# RobotCtrl_Core.net
KiCad netlist of a schematic drawn in Altium Designer
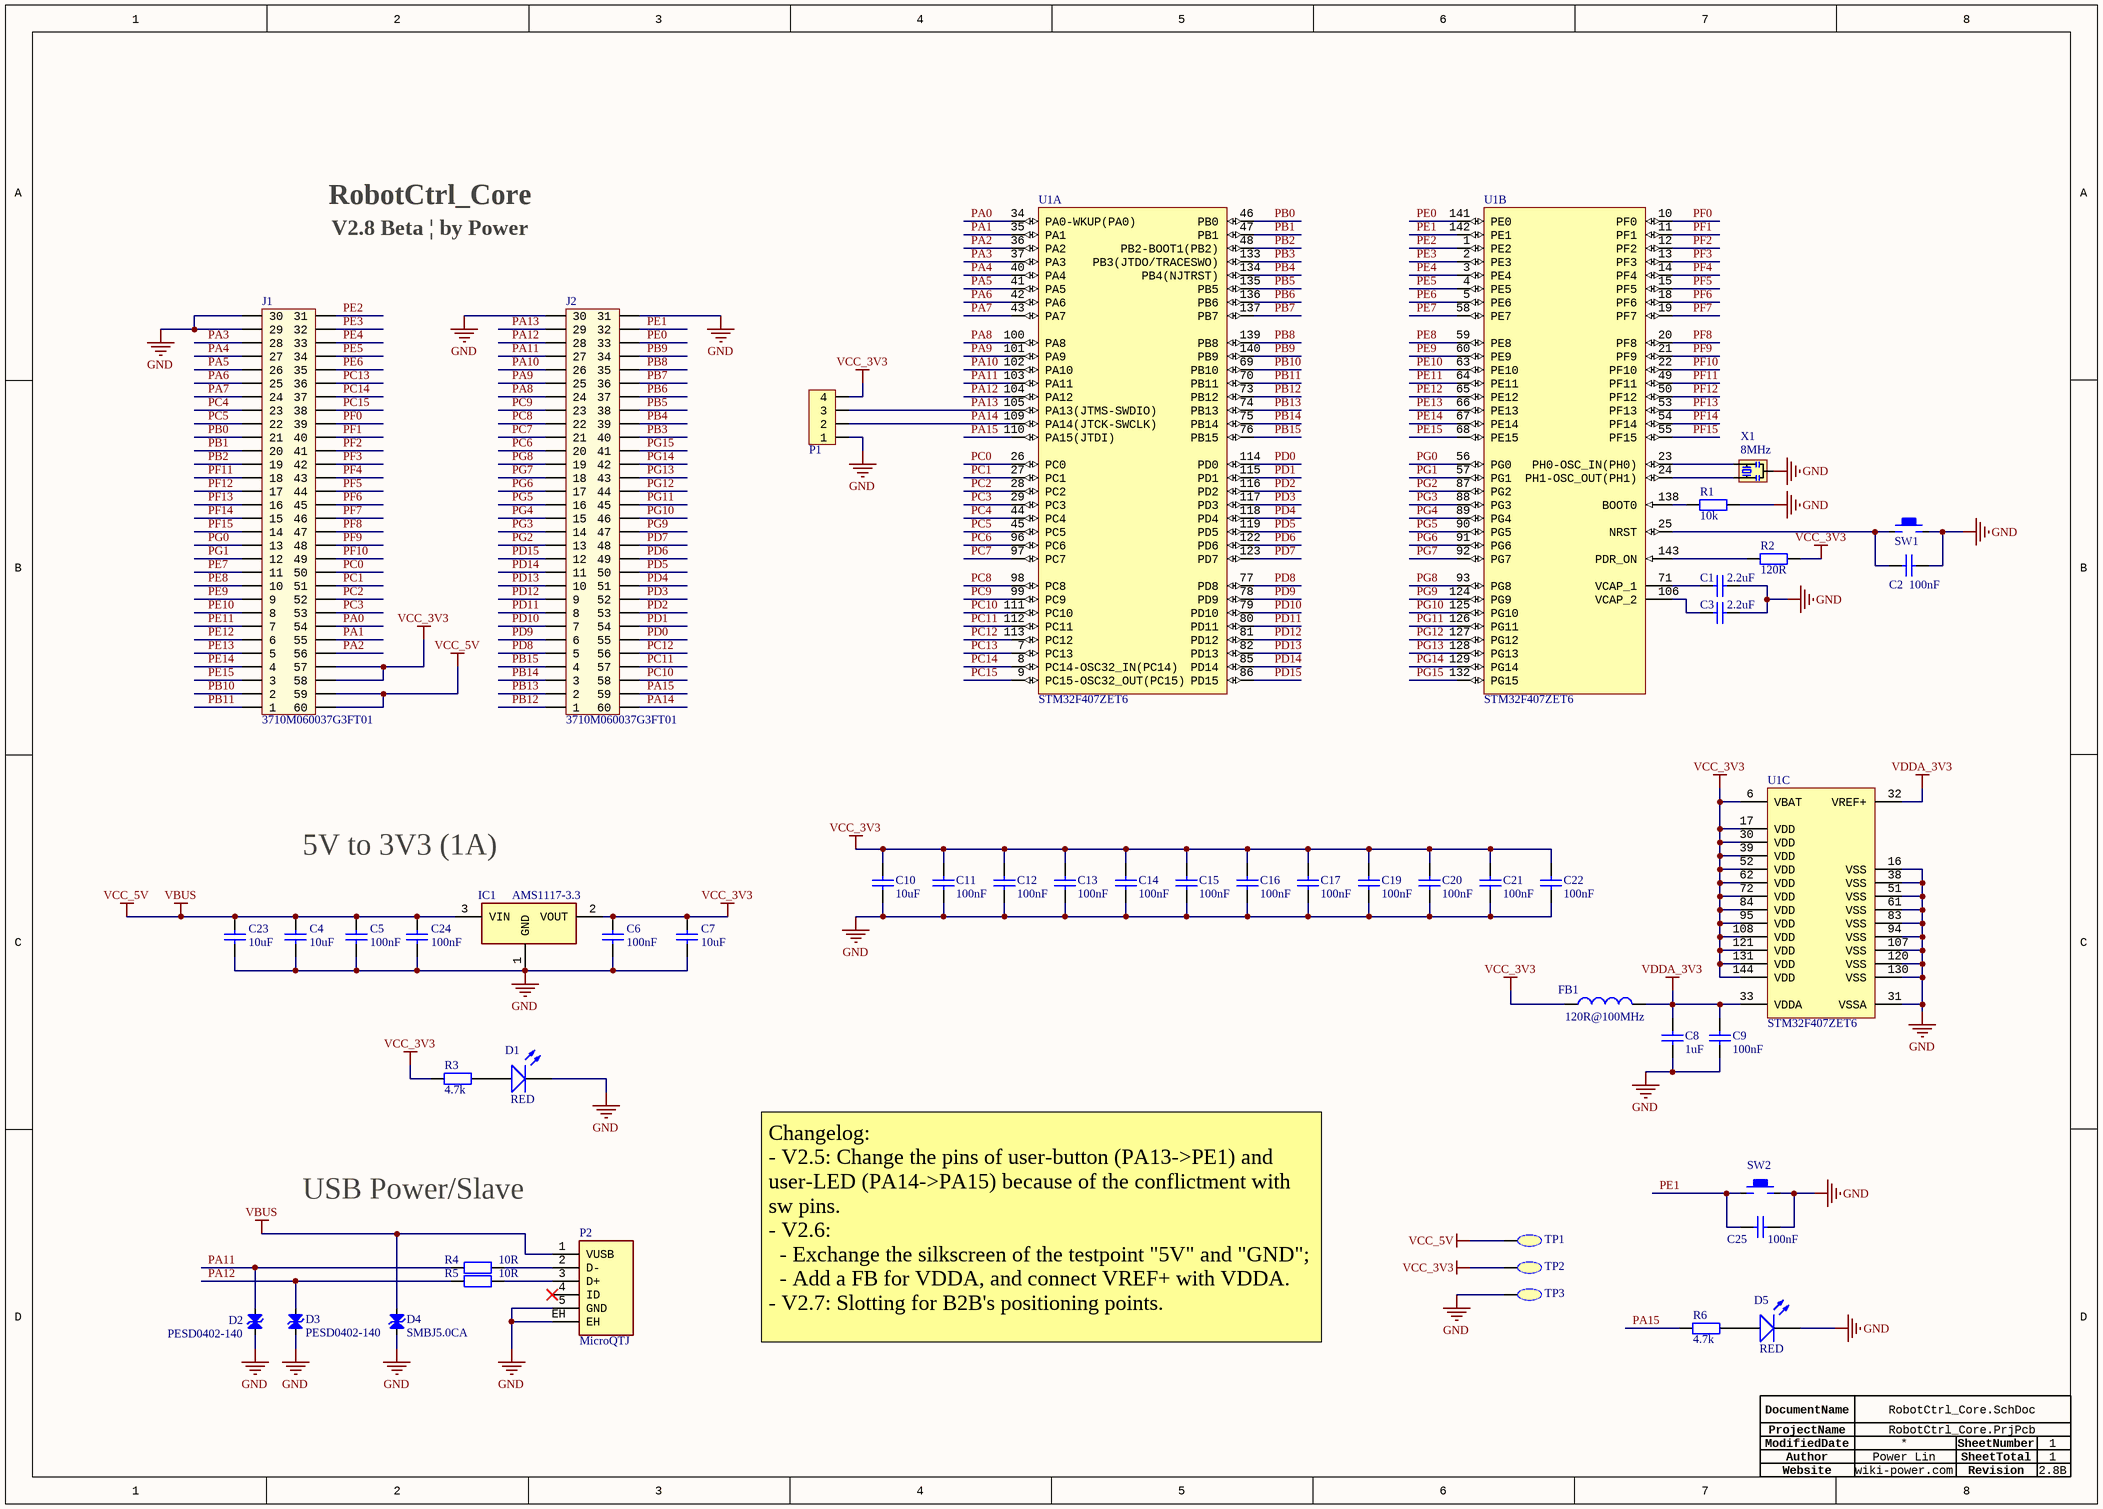
[diagram p0: RobotCtrl_Core.SchDoc]

(export (version "E")
  (design (tool "Eeschema 10.0.6"))
  (components
    (comp (ref "C1")
      (value "2.2uF")
      (footprint "CAP-0603")
      (description "贴片电容")
      (libsource (lib "Power_Lib_Altium") (part "CAP"))
    )
    (comp (ref "C2")
      (value "100nF")
      (footprint "CAP-0603")
      (description "贴片电容")
      (libsource (lib "Power_Lib_Altium") (part "CAP"))
    )
    (comp (ref "C3")
      (value "2.2uF")
      (footprint "CAP-0603")
      (description "贴片电容")
      (libsource (lib "Power_Lib_Altium") (part "CAP"))
    )
    (comp (ref "C4")
      (value "10uF")
      (footprint "CAP-0603")
      (description "贴片电容")
      (libsource (lib "Power_Lib_Altium") (part "CAP"))
    )
    (comp (ref "C5")
      (value "100nF")
      (footprint "CAP-0603")
      (description "贴片电容")
      (libsource (lib "Power_Lib_Altium") (part "CAP"))
    )
    (comp (ref "C6")
      (value "100nF")
      (footprint "CAP-0603")
      (description "贴片电容")
      (libsource (lib "Power_Lib_Altium") (part "CAP"))
    )
    (comp (ref "C7")
      (value "10uF")
      (footprint "CAP-0603")
      (description "贴片电容")
      (libsource (lib "Power_Lib_Altium") (part "CAP"))
    )
    (comp (ref "C8")
      (value "1uF")
      (footprint "CAP-0402")
      (description "贴片电容")
      (libsource (lib "Power_Lib_Altium") (part "CAP"))
    )
    (comp (ref "C9")
      (value "100nF")
      (footprint "CAP-0402")
      (description "贴片电容")
      (libsource (lib "Power_Lib_Altium") (part "CAP"))
    )
    (comp (ref "C10")
      (value "10uF")
      (footprint "CAP-0402")
      (description "贴片电容")
      (libsource (lib "Power_Lib_Altium") (part "CAP"))
    )
    (comp (ref "C11")
      (value "100nF")
      (footprint "CAP-0402")
      (description "贴片电容")
      (libsource (lib "Power_Lib_Altium") (part "CAP"))
    )
    (comp (ref "C12")
      (value "100nF")
      (footprint "CAP-0402")
      (description "贴片电容")
      (libsource (lib "Power_Lib_Altium") (part "CAP"))
    )
    (comp (ref "C13")
      (value "100nF")
      (footprint "CAP-0402")
      (description "贴片电容")
      (libsource (lib "Power_Lib_Altium") (part "CAP"))
    )
    (comp (ref "C14")
      (value "100nF")
      (footprint "CAP-0402")
      (description "贴片电容")
      (libsource (lib "Power_Lib_Altium") (part "CAP"))
    )
    (comp (ref "C15")
      (value "100nF")
      (footprint "CAP-0402")
      (description "贴片电容")
      (libsource (lib "Power_Lib_Altium") (part "CAP"))
    )
    (comp (ref "C16")
      (value "100nF")
      (footprint "CAP-0402")
      (description "贴片电容")
      (libsource (lib "Power_Lib_Altium") (part "CAP"))
    )
    (comp (ref "C17")
      (value "100nF")
      (footprint "CAP-0402")
      (description "贴片电容")
      (libsource (lib "Power_Lib_Altium") (part "CAP"))
    )
    (comp (ref "C19")
      (value "100nF")
      (footprint "CAP-0402")
      (description "贴片电容")
      (libsource (lib "Power_Lib_Altium") (part "CAP"))
    )
    (comp (ref "C20")
      (value "100nF")
      (footprint "CAP-0402")
      (description "贴片电容")
      (libsource (lib "Power_Lib_Altium") (part "CAP"))
    )
    (comp (ref "C21")
      (value "100nF")
      (footprint "CAP-0402")
      (description "贴片电容")
      (libsource (lib "Power_Lib_Altium") (part "CAP"))
    )
    (comp (ref "C22")
      (value "100nF")
      (footprint "CAP-0402")
      (description "贴片电容")
      (libsource (lib "Power_Lib_Altium") (part "CAP"))
    )
    (comp (ref "C23")
      (value "10uF")
      (footprint "CAP-0603")
      (description "贴片电容")
      (libsource (lib "Power_Lib_Altium") (part "CAP"))
    )
    (comp (ref "C24")
      (value "100nF")
      (footprint "CAP-0603")
      (description "贴片电容")
      (libsource (lib "Power_Lib_Altium") (part "CAP"))
    )
    (comp (ref "C25")
      (value "100nF")
      (footprint "CAP-0603")
      (description "贴片电容")
      (libsource (lib "Power_Lib_Altium") (part "CAP"))
    )
    (comp (ref "D1")
      (value "RED")
      (footprint "LED-0603")
      (description "发光二极管")
      (libsource (lib "Power_Lib_Altium") (part "LED"))
    )
    (comp (ref "D2")
      (value "PESD0402-140")
      (footprint "D-0402")
      (libsource (lib "Power_Lib_Altium") (part "TVS_C"))
    )
    (comp (ref "D3")
      (value "PESD0402-140")
      (footprint "D-0402")
      (libsource (lib "Power_Lib_Altium") (part "TVS_C"))
    )
    (comp (ref "D4")
      (value "SMBJ5.0CA")
      (footprint "DO-214AA/SMB")
      (description "Brightking / MDD")
      (libsource (lib "Power_Lib_Altium") (part "TVS_C"))
    )
    (comp (ref "D5")
      (value "RED")
      (footprint "LED-0603")
      (description "发光二极管")
      (libsource (lib "Power_Lib_Altium") (part "LED"))
    )
    (comp (ref "FB1")
      (value "120R@100MHz")
      (footprint "CAP-0402")
      (description "BLM15AG121SN1D")
      (libsource (lib "Power_Lib_Altium") (part "BEAD"))
    )
    (comp (ref "IC1")
      (value "AMS1117-3.3")
      (footprint "SOT-223")
      (description "AMS1117-3.3 1.0A")
      (fields (field (name "MANUFACTURER_PART_NUMBER") "SI2302DS") (field (name "RS PART NUMBER") "7983053P"))
      (libsource (lib "Power_Lib_Altium") (part "AMS1117"))
    )
    (comp (ref "J1")
      (value "3710M060037G3FT01")
      (footprint "3710M060037G3FT01")
      (description "B2B Connector")
      (libsource (lib "Power_Lib_Altium") (part "3710M/F"))
    )
    (comp (ref "J2")
      (value "3710M060037G3FT01")
      (footprint "3710M060037G3FT01")
      (description "B2B Connector")
      (libsource (lib "Power_Lib_Altium") (part "3710M/F"))
    )
    (comp (ref "P1")
      (value "HDR1x4_2.54")
      (footprint "HDR1X4_2.54")
      (description "Header")
      (libsource (lib "Power_Lib_Altium") (part "HDR1x4_2.54"))
    )
    (comp (ref "P2")
      (value "MicroQTJ")
      (footprint "USB-MICRO")
      (description "USB_MICRO")
      (libsource (lib "Power_Lib_Altium") (part "USB_MICRO"))
    )
    (comp (ref "R1")
      (value "10k")
      (footprint "R-0603")
      (description "贴片电阻")
      (libsource (lib "Power_Lib_Altium") (part "RES"))
    )
    (comp (ref "R2")
      (value "120R")
      (footprint "R-0603")
      (description "贴片电阻")
      (libsource (lib "Power_Lib_Altium") (part "RES"))
    )
    (comp (ref "R3")
      (value "4.7k")
      (footprint "R-0603")
      (description "贴片电阻")
      (libsource (lib "Power_Lib_Altium") (part "RES"))
    )
    (comp (ref "R4")
      (value "10R")
      (footprint "R-0603")
      (description "贴片电阻")
      (libsource (lib "") (part "RES_1"))
    )
    (comp (ref "R5")
      (value "10R")
      (footprint "R-0603")
      (description "贴片电阻")
      (libsource (lib "") (part "RES_1"))
    )
    (comp (ref "R6")
      (value "4.7k")
      (footprint "R-0603")
      (description "贴片电阻")
      (libsource (lib "Power_Lib_Altium") (part "RES"))
    )
    (comp (ref "SW1")
      (value "KEY")
      (footprint "KEY-4P-4.2*3.4*2.5")
      (description "按键开关")
      (libsource (lib "Power_Lib_Altium") (part "KEY"))
    )
    (comp (ref "SW2")
      (value "KEY")
      (footprint "KEY-4P-4.2*3.4*2.5")
      (description "按键开关")
      (libsource (lib "Power_Lib_Altium") (part "KEY"))
    )
    (comp (ref "TP1")
      (value "TestPoint")
      (footprint "TestPoint")
      (description "测试点")
      (libsource (lib "Power_Lib_Altium") (part "TestPoint"))
    )
    (comp (ref "TP2")
      (value "TestPoint")
      (footprint "TestPoint")
      (description "测试点")
      (libsource (lib "Power_Lib_Altium") (part "TestPoint"))
    )
    (comp (ref "TP3")
      (value "TestPoint")
      (footprint "TestPoint")
      (description "测试点")
      (libsource (lib "Power_Lib_Altium") (part "TestPoint"))
    )
    (comp (ref "U1")
      (value "STM32F407ZET6")
      (footprint "STM-LQFP144_N")
      (fields (field (name "MANUFACTURER") "STMicroelectronics"))
      (libsource (lib "Power_Lib_Altium") (part "STM32F407ZET6"))
    )
    (comp (ref "X1")
      (value "8MHz")
      (footprint "SMD3213-3P")
      (description "CSTCE8M00G15C99-R0")
      (libsource (lib "Power_Lib_Altium") (part "XTAL"))
    )
  )
  (nets
    (net (code "1") (name "/PA0") (class "Default")
      (node (ref "J1") (pin "54") (pinfunction "54_54") (pintype "passive"))
      (node (ref "U1") (pin "34") (pinfunction "PA0-WKUP(PA0)_34") (pintype "bidirectional"))
    )
    (net (code "2") (name "/PA1") (class "Default")
      (node (ref "J1") (pin "55") (pinfunction "55_55") (pintype "passive"))
      (node (ref "U1") (pin "35") (pinfunction "PA1_35") (pintype "bidirectional"))
    )
    (net (code "3") (name "/PA2") (class "Default")
      (node (ref "J1") (pin "56") (pinfunction "56_56") (pintype "passive"))
      (node (ref "U1") (pin "36") (pinfunction "PA2_36") (pintype "bidirectional"))
    )
    (net (code "4") (name "/PA3") (class "Default")
      (node (ref "J1") (pin "28") (pinfunction "28_28") (pintype "passive"))
      (node (ref "U1") (pin "37") (pinfunction "PA3_37") (pintype "bidirectional"))
    )
    (net (code "5") (name "/PA4") (class "Default")
      (node (ref "J1") (pin "27") (pinfunction "27_27") (pintype "passive"))
      (node (ref "U1") (pin "40") (pinfunction "PA4_40") (pintype "bidirectional"))
    )
    (net (code "6") (name "/PA5") (class "Default")
      (node (ref "J1") (pin "26") (pinfunction "26_26") (pintype "passive"))
      (node (ref "U1") (pin "41") (pinfunction "PA5_41") (pintype "bidirectional"))
    )
    (net (code "7") (name "/PA6") (class "Default")
      (node (ref "J1") (pin "25") (pinfunction "25_25") (pintype "passive"))
      (node (ref "U1") (pin "42") (pinfunction "PA6_42") (pintype "bidirectional"))
    )
    (net (code "8") (name "/PA7") (class "Default")
      (node (ref "J1") (pin "24") (pinfunction "24_24") (pintype "passive"))
      (node (ref "U1") (pin "43") (pinfunction "PA7_43") (pintype "bidirectional"))
    )
    (net (code "9") (name "/PA8") (class "Default")
      (node (ref "J2") (pin "24") (pinfunction "24_24") (pintype "passive"))
      (node (ref "U1") (pin "100") (pinfunction "PA8_100") (pintype "bidirectional"))
    )
    (net (code "10") (name "/PA9") (class "Default")
      (node (ref "J2") (pin "25") (pinfunction "25_25") (pintype "passive"))
      (node (ref "U1") (pin "101") (pinfunction "PA9_101") (pintype "bidirectional"))
    )
    (net (code "11") (name "/PA10") (class "Default")
      (node (ref "J2") (pin "26") (pinfunction "26_26") (pintype "passive"))
      (node (ref "U1") (pin "102") (pinfunction "PA10_102") (pintype "bidirectional"))
    )
    (net (code "12") (name "/PA11") (class "Default")
      (node (ref "D2") (pin "2") (pinfunction "2_2") (pintype "passive"))
      (node (ref "J2") (pin "27") (pinfunction "27_27") (pintype "passive"))
      (node (ref "R4") (pin "1") (pinfunction "1_1") (pintype "passive"))
      (node (ref "U1") (pin "103") (pinfunction "PA11_103") (pintype "bidirectional"))
    )
    (net (code "13") (name "/PA12") (class "Default")
      (node (ref "D3") (pin "2") (pinfunction "2_2") (pintype "passive"))
      (node (ref "J2") (pin "28") (pinfunction "28_28") (pintype "passive"))
      (node (ref "R5") (pin "1") (pinfunction "1_1") (pintype "passive"))
      (node (ref "U1") (pin "104") (pinfunction "PA12_104") (pintype "bidirectional"))
    )
    (net (code "14") (name "/PA13") (class "Default")
      (node (ref "J2") (pin "29") (pinfunction "29_29") (pintype "passive"))
      (node (ref "P1") (pin "3") (pinfunction "3_3") (pintype "passive"))
      (node (ref "U1") (pin "105") (pinfunction "PA13(JTMS-SWDIO)_105") (pintype "bidirectional"))
    )
    (net (code "15") (name "/PA14") (class "Default")
      (node (ref "J2") (pin "60") (pinfunction "60_60") (pintype "passive"))
      (node (ref "P1") (pin "2") (pinfunction "2_2") (pintype "passive"))
      (node (ref "U1") (pin "109") (pinfunction "PA14(JTCK-SWCLK)_109") (pintype "bidirectional"))
    )
    (net (code "16") (name "/PA15") (class "Default")
      (node (ref "J2") (pin "59") (pinfunction "59_59") (pintype "passive"))
      (node (ref "R6") (pin "2") (pinfunction "2_2") (pintype "passive"))
      (node (ref "U1") (pin "110") (pinfunction "PA15(JTDI)_110") (pintype "bidirectional"))
    )
    (net (code "17") (name "/PB0") (class "Default")
      (node (ref "J1") (pin "21") (pinfunction "21_21") (pintype "passive"))
      (node (ref "U1") (pin "46") (pinfunction "PB0_46") (pintype "bidirectional"))
    )
    (net (code "18") (name "/PB1") (class "Default")
      (node (ref "J1") (pin "20") (pinfunction "20_20") (pintype "passive"))
      (node (ref "U1") (pin "47") (pinfunction "PB1_47") (pintype "bidirectional"))
    )
    (net (code "19") (name "/PB2") (class "Default")
      (node (ref "J1") (pin "19") (pinfunction "19_19") (pintype "passive"))
      (node (ref "U1") (pin "48") (pinfunction "PB2-BOOT1(PB2)_48") (pintype "bidirectional"))
    )
    (net (code "20") (name "/PB3") (class "Default")
      (node (ref "J2") (pin "40") (pinfunction "40_40") (pintype "passive"))
      (node (ref "U1") (pin "133") (pinfunction "PB3(JTDO/TRACESWO)_133") (pintype "bidirectional"))
    )
    (net (code "21") (name "/PB4") (class "Default")
      (node (ref "J2") (pin "39") (pinfunction "39_39") (pintype "passive"))
      (node (ref "U1") (pin "134") (pinfunction "PB4(NJTRST)_134") (pintype "bidirectional"))
    )
    (net (code "22") (name "/PB5") (class "Default")
      (node (ref "J2") (pin "38") (pinfunction "38_38") (pintype "passive"))
      (node (ref "U1") (pin "135") (pinfunction "PB5_135") (pintype "bidirectional"))
    )
    (net (code "23") (name "/PB6") (class "Default")
      (node (ref "J2") (pin "37") (pinfunction "37_37") (pintype "passive"))
      (node (ref "U1") (pin "136") (pinfunction "PB6_136") (pintype "bidirectional"))
    )
    (net (code "24") (name "/PB7") (class "Default")
      (node (ref "J2") (pin "36") (pinfunction "36_36") (pintype "passive"))
      (node (ref "U1") (pin "137") (pinfunction "PB7_137") (pintype "bidirectional"))
    )
    (net (code "25") (name "/PB8") (class "Default")
      (node (ref "J2") (pin "35") (pinfunction "35_35") (pintype "passive"))
      (node (ref "U1") (pin "139") (pinfunction "PB8_139") (pintype "bidirectional"))
    )
    (net (code "26") (name "/PB9") (class "Default")
      (node (ref "J2") (pin "34") (pinfunction "34_34") (pintype "passive"))
      (node (ref "U1") (pin "140") (pinfunction "PB9_140") (pintype "bidirectional"))
    )
    (net (code "27") (name "/PB10") (class "Default")
      (node (ref "J1") (pin "2") (pinfunction "2_2") (pintype "passive"))
      (node (ref "U1") (pin "69") (pinfunction "PB10_69") (pintype "bidirectional"))
    )
    (net (code "28") (name "/PB11") (class "Default")
      (node (ref "J1") (pin "1") (pinfunction "1_1") (pintype "passive"))
      (node (ref "U1") (pin "70") (pinfunction "PB11_70") (pintype "bidirectional"))
    )
    (net (code "29") (name "/PB12") (class "Default")
      (node (ref "J2") (pin "1") (pinfunction "1_1") (pintype "passive"))
      (node (ref "U1") (pin "73") (pinfunction "PB12_73") (pintype "bidirectional"))
    )
    (net (code "30") (name "/PB13") (class "Default")
      (node (ref "J2") (pin "2") (pinfunction "2_2") (pintype "passive"))
      (node (ref "U1") (pin "74") (pinfunction "PB13_74") (pintype "bidirectional"))
    )
    (net (code "31") (name "/PB14") (class "Default")
      (node (ref "J2") (pin "3") (pinfunction "3_3") (pintype "passive"))
      (node (ref "U1") (pin "75") (pinfunction "PB14_75") (pintype "bidirectional"))
    )
    (net (code "32") (name "/PB15") (class "Default")
      (node (ref "J2") (pin "4") (pinfunction "4_4") (pintype "passive"))
      (node (ref "U1") (pin "76") (pinfunction "PB15_76") (pintype "bidirectional"))
    )
    (net (code "33") (name "/PC0") (class "Default")
      (node (ref "J1") (pin "50") (pinfunction "50_50") (pintype "passive"))
      (node (ref "U1") (pin "26") (pinfunction "PC0_26") (pintype "bidirectional"))
    )
    (net (code "34") (name "/PC1") (class "Default")
      (node (ref "J1") (pin "51") (pinfunction "51_51") (pintype "passive"))
      (node (ref "U1") (pin "27") (pinfunction "PC1_27") (pintype "bidirectional"))
    )
    (net (code "35") (name "/PC2") (class "Default")
      (node (ref "J1") (pin "52") (pinfunction "52_52") (pintype "passive"))
      (node (ref "U1") (pin "28") (pinfunction "PC2_28") (pintype "bidirectional"))
    )
    (net (code "36") (name "/PC3") (class "Default")
      (node (ref "J1") (pin "53") (pinfunction "53_53") (pintype "passive"))
      (node (ref "U1") (pin "29") (pinfunction "PC3_29") (pintype "bidirectional"))
    )
    (net (code "37") (name "/PC4") (class "Default")
      (node (ref "J1") (pin "23") (pinfunction "23_23") (pintype "passive"))
      (node (ref "U1") (pin "44") (pinfunction "PC4_44") (pintype "bidirectional"))
    )
    (net (code "38") (name "/PC5") (class "Default")
      (node (ref "J1") (pin "22") (pinfunction "22_22") (pintype "passive"))
      (node (ref "U1") (pin "45") (pinfunction "PC5_45") (pintype "bidirectional"))
    )
    (net (code "39") (name "/PC6") (class "Default")
      (node (ref "J2") (pin "20") (pinfunction "20_20") (pintype "passive"))
      (node (ref "U1") (pin "96") (pinfunction "PC6_96") (pintype "bidirectional"))
    )
    (net (code "40") (name "/PC7") (class "Default")
      (node (ref "J2") (pin "21") (pinfunction "21_21") (pintype "passive"))
      (node (ref "U1") (pin "97") (pinfunction "PC7_97") (pintype "bidirectional"))
    )
    (net (code "41") (name "/PC8") (class "Default")
      (node (ref "J2") (pin "22") (pinfunction "22_22") (pintype "passive"))
      (node (ref "U1") (pin "98") (pinfunction "PC8_98") (pintype "bidirectional"))
    )
    (net (code "42") (name "/PC9") (class "Default")
      (node (ref "J2") (pin "23") (pinfunction "23_23") (pintype "passive"))
      (node (ref "U1") (pin "99") (pinfunction "PC9_99") (pintype "bidirectional"))
    )
    (net (code "43") (name "/PC10") (class "Default")
      (node (ref "J2") (pin "58") (pinfunction "58_58") (pintype "passive"))
      (node (ref "U1") (pin "111") (pinfunction "PC10_111") (pintype "bidirectional"))
    )
    (net (code "44") (name "/PC11") (class "Default")
      (node (ref "J2") (pin "57") (pinfunction "57_57") (pintype "passive"))
      (node (ref "U1") (pin "112") (pinfunction "PC11_112") (pintype "bidirectional"))
    )
    (net (code "45") (name "/PC12") (class "Default")
      (node (ref "J2") (pin "56") (pinfunction "56_56") (pintype "passive"))
      (node (ref "U1") (pin "113") (pinfunction "PC12_113") (pintype "bidirectional"))
    )
    (net (code "46") (name "/PC13") (class "Default")
      (node (ref "J1") (pin "36") (pinfunction "36_36") (pintype "passive"))
      (node (ref "U1") (pin "7") (pinfunction "PC13_7") (pintype "bidirectional"))
    )
    (net (code "47") (name "/PC14") (class "Default")
      (node (ref "J1") (pin "37") (pinfunction "37_37") (pintype "passive"))
      (node (ref "U1") (pin "8") (pinfunction "PC14-OSC32_IN(PC14)_8") (pintype "bidirectional"))
    )
    (net (code "48") (name "/PC15") (class "Default")
      (node (ref "J1") (pin "38") (pinfunction "38_38") (pintype "passive"))
      (node (ref "U1") (pin "9") (pinfunction "PC15-OSC32_OUT(PC15)_9") (pintype "bidirectional"))
    )
    (net (code "49") (name "/PD0") (class "Default")
      (node (ref "J2") (pin "55") (pinfunction "55_55") (pintype "passive"))
      (node (ref "U1") (pin "114") (pinfunction "PD0_114") (pintype "bidirectional"))
    )
    (net (code "50") (name "/PD1") (class "Default")
      (node (ref "J2") (pin "54") (pinfunction "54_54") (pintype "passive"))
      (node (ref "U1") (pin "115") (pinfunction "PD1_115") (pintype "bidirectional"))
    )
    (net (code "51") (name "/PD2") (class "Default")
      (node (ref "J2") (pin "53") (pinfunction "53_53") (pintype "passive"))
      (node (ref "U1") (pin "116") (pinfunction "PD2_116") (pintype "bidirectional"))
    )
    (net (code "52") (name "/PD3") (class "Default")
      (node (ref "J2") (pin "52") (pinfunction "52_52") (pintype "passive"))
      (node (ref "U1") (pin "117") (pinfunction "PD3_117") (pintype "bidirectional"))
    )
    (net (code "53") (name "/PD4") (class "Default")
      (node (ref "J2") (pin "51") (pinfunction "51_51") (pintype "passive"))
      (node (ref "U1") (pin "118") (pinfunction "PD4_118") (pintype "bidirectional"))
    )
    (net (code "54") (name "/PD5") (class "Default")
      (node (ref "J2") (pin "50") (pinfunction "50_50") (pintype "passive"))
      (node (ref "U1") (pin "119") (pinfunction "PD5_119") (pintype "bidirectional"))
    )
    (net (code "55") (name "/PD6") (class "Default")
      (node (ref "J2") (pin "49") (pinfunction "49_49") (pintype "passive"))
      (node (ref "U1") (pin "122") (pinfunction "PD6_122") (pintype "bidirectional"))
    )
    (net (code "56") (name "/PD7") (class "Default")
      (node (ref "J2") (pin "48") (pinfunction "48_48") (pintype "passive"))
      (node (ref "U1") (pin "123") (pinfunction "PD7_123") (pintype "bidirectional"))
    )
    (net (code "57") (name "/PD8") (class "Default")
      (node (ref "J2") (pin "5") (pinfunction "5_5") (pintype "passive"))
      (node (ref "U1") (pin "77") (pinfunction "PD8_77") (pintype "bidirectional"))
    )
    (net (code "58") (name "/PD9") (class "Default")
      (node (ref "J2") (pin "6") (pinfunction "6_6") (pintype "passive"))
      (node (ref "U1") (pin "78") (pinfunction "PD9_78") (pintype "bidirectional"))
    )
    (net (code "59") (name "/PD10") (class "Default")
      (node (ref "J2") (pin "7") (pinfunction "7_7") (pintype "passive"))
      (node (ref "U1") (pin "79") (pinfunction "PD10_79") (pintype "bidirectional"))
    )
    (net (code "60") (name "/PD11") (class "Default")
      (node (ref "J2") (pin "8") (pinfunction "8_8") (pintype "passive"))
      (node (ref "U1") (pin "80") (pinfunction "PD11_80") (pintype "bidirectional"))
    )
    (net (code "61") (name "/PD12") (class "Default")
      (node (ref "J2") (pin "9") (pinfunction "9_9") (pintype "passive"))
      (node (ref "U1") (pin "81") (pinfunction "PD12_81") (pintype "bidirectional"))
    )
    (net (code "62") (name "/PD13") (class "Default")
      (node (ref "J2") (pin "10") (pinfunction "10_10") (pintype "passive"))
      (node (ref "U1") (pin "82") (pinfunction "PD13_82") (pintype "bidirectional"))
    )
    (net (code "63") (name "/PD14") (class "Default")
      (node (ref "J2") (pin "11") (pinfunction "11_11") (pintype "passive"))
      (node (ref "U1") (pin "85") (pinfunction "PD14_85") (pintype "bidirectional"))
    )
    (net (code "64") (name "/PD15") (class "Default")
      (node (ref "J2") (pin "12") (pinfunction "12_12") (pintype "passive"))
      (node (ref "U1") (pin "86") (pinfunction "PD15_86") (pintype "bidirectional"))
    )
    (net (code "65") (name "/PE0") (class "Default")
      (node (ref "J2") (pin "33") (pinfunction "33_33") (pintype "passive"))
      (node (ref "U1") (pin "141") (pinfunction "PE0_141") (pintype "bidirectional"))
    )
    (net (code "66") (name "/PE1") (class "Default")
      (node (ref "C25") (pin "2") (pinfunction "2_2") (pintype "passive"))
      (node (ref "J2") (pin "32") (pinfunction "32_32") (pintype "passive"))
      (node (ref "SW2") (pin "1") (pinfunction "1_1") (pintype "passive"))
      (node (ref "U1") (pin "142") (pinfunction "PE1_142") (pintype "bidirectional"))
    )
    (net (code "67") (name "/PE2") (class "Default")
      (node (ref "J1") (pin "31") (pinfunction "31_31") (pintype "passive"))
      (node (ref "U1") (pin "1") (pinfunction "PE2_1") (pintype "bidirectional"))
    )
    (net (code "68") (name "/PE3") (class "Default")
      (node (ref "J1") (pin "32") (pinfunction "32_32") (pintype "passive"))
      (node (ref "U1") (pin "2") (pinfunction "PE3_2") (pintype "bidirectional"))
    )
    (net (code "69") (name "/PE4") (class "Default")
      (node (ref "J1") (pin "33") (pinfunction "33_33") (pintype "passive"))
      (node (ref "U1") (pin "3") (pinfunction "PE4_3") (pintype "bidirectional"))
    )
    (net (code "70") (name "/PE5") (class "Default")
      (node (ref "J1") (pin "34") (pinfunction "34_34") (pintype "passive"))
      (node (ref "U1") (pin "4") (pinfunction "PE5_4") (pintype "bidirectional"))
    )
    (net (code "71") (name "/PE6") (class "Default")
      (node (ref "J1") (pin "35") (pinfunction "35_35") (pintype "passive"))
      (node (ref "U1") (pin "5") (pinfunction "PE6_5") (pintype "bidirectional"))
    )
    (net (code "72") (name "/PE7") (class "Default")
      (node (ref "J1") (pin "11") (pinfunction "11_11") (pintype "passive"))
      (node (ref "U1") (pin "58") (pinfunction "PE7_58") (pintype "bidirectional"))
    )
    (net (code "73") (name "/PE8") (class "Default")
      (node (ref "J1") (pin "10") (pinfunction "10_10") (pintype "passive"))
      (node (ref "U1") (pin "59") (pinfunction "PE8_59") (pintype "bidirectional"))
    )
    (net (code "74") (name "/PE9") (class "Default")
      (node (ref "J1") (pin "9") (pinfunction "9_9") (pintype "passive"))
      (node (ref "U1") (pin "60") (pinfunction "PE9_60") (pintype "bidirectional"))
    )
    (net (code "75") (name "/PE10") (class "Default")
      (node (ref "J1") (pin "8") (pinfunction "8_8") (pintype "passive"))
      (node (ref "U1") (pin "63") (pinfunction "PE10_63") (pintype "bidirectional"))
    )
    (net (code "76") (name "/PE11") (class "Default")
      (node (ref "J1") (pin "7") (pinfunction "7_7") (pintype "passive"))
      (node (ref "U1") (pin "64") (pinfunction "PE11_64") (pintype "bidirectional"))
    )
    (net (code "77") (name "/PE12") (class "Default")
      (node (ref "J1") (pin "6") (pinfunction "6_6") (pintype "passive"))
      (node (ref "U1") (pin "65") (pinfunction "PE12_65") (pintype "bidirectional"))
    )
    (net (code "78") (name "/PE13") (class "Default")
      (node (ref "J1") (pin "5") (pinfunction "5_5") (pintype "passive"))
      (node (ref "U1") (pin "66") (pinfunction "PE13_66") (pintype "bidirectional"))
    )
    (net (code "79") (name "/PE14") (class "Default")
      (node (ref "J1") (pin "4") (pinfunction "4_4") (pintype "passive"))
      (node (ref "U1") (pin "67") (pinfunction "PE14_67") (pintype "bidirectional"))
    )
    (net (code "80") (name "/PE15") (class "Default")
      (node (ref "J1") (pin "3") (pinfunction "3_3") (pintype "passive"))
      (node (ref "U1") (pin "68") (pinfunction "PE15_68") (pintype "bidirectional"))
    )
    (net (code "81") (name "/PF0") (class "Default")
      (node (ref "J1") (pin "39") (pinfunction "39_39") (pintype "passive"))
      (node (ref "U1") (pin "10") (pinfunction "PF0_10") (pintype "bidirectional"))
    )
    (net (code "82") (name "/PF1") (class "Default")
      (node (ref "J1") (pin "40") (pinfunction "40_40") (pintype "passive"))
      (node (ref "U1") (pin "11") (pinfunction "PF1_11") (pintype "bidirectional"))
    )
    (net (code "83") (name "/PF2") (class "Default")
      (node (ref "J1") (pin "41") (pinfunction "41_41") (pintype "passive"))
      (node (ref "U1") (pin "12") (pinfunction "PF2_12") (pintype "bidirectional"))
    )
    (net (code "84") (name "/PF3") (class "Default")
      (node (ref "J1") (pin "42") (pinfunction "42_42") (pintype "passive"))
      (node (ref "U1") (pin "13") (pinfunction "PF3_13") (pintype "bidirectional"))
    )
    (net (code "85") (name "/PF4") (class "Default")
      (node (ref "J1") (pin "43") (pinfunction "43_43") (pintype "passive"))
      (node (ref "U1") (pin "14") (pinfunction "PF4_14") (pintype "bidirectional"))
    )
    (net (code "86") (name "/PF5") (class "Default")
      (node (ref "J1") (pin "44") (pinfunction "44_44") (pintype "passive"))
      (node (ref "U1") (pin "15") (pinfunction "PF5_15") (pintype "bidirectional"))
    )
    (net (code "87") (name "/PF6") (class "Default")
      (node (ref "J1") (pin "45") (pinfunction "45_45") (pintype "passive"))
      (node (ref "U1") (pin "18") (pinfunction "PF6_18") (pintype "bidirectional"))
    )
    (net (code "88") (name "/PF7") (class "Default")
      (node (ref "J1") (pin "46") (pinfunction "46_46") (pintype "passive"))
      (node (ref "U1") (pin "19") (pinfunction "PF7_19") (pintype "bidirectional"))
    )
    (net (code "89") (name "/PF8") (class "Default")
      (node (ref "J1") (pin "47") (pinfunction "47_47") (pintype "passive"))
      (node (ref "U1") (pin "20") (pinfunction "PF8_20") (pintype "bidirectional"))
    )
    (net (code "90") (name "/PF9") (class "Default")
      (node (ref "J1") (pin "48") (pinfunction "48_48") (pintype "passive"))
      (node (ref "U1") (pin "21") (pinfunction "PF9_21") (pintype "bidirectional"))
    )
    (net (code "91") (name "/PF10") (class "Default")
      (node (ref "J1") (pin "49") (pinfunction "49_49") (pintype "passive"))
      (node (ref "U1") (pin "22") (pinfunction "PF10_22") (pintype "bidirectional"))
    )
    (net (code "92") (name "/PF11") (class "Default")
      (node (ref "J1") (pin "18") (pinfunction "18_18") (pintype "passive"))
      (node (ref "U1") (pin "49") (pinfunction "PF11_49") (pintype "bidirectional"))
    )
    (net (code "93") (name "/PF12") (class "Default")
      (node (ref "J1") (pin "17") (pinfunction "17_17") (pintype "passive"))
      (node (ref "U1") (pin "50") (pinfunction "PF12_50") (pintype "bidirectional"))
    )
    (net (code "94") (name "/PF13") (class "Default")
      (node (ref "J1") (pin "16") (pinfunction "16_16") (pintype "passive"))
      (node (ref "U1") (pin "53") (pinfunction "PF13_53") (pintype "bidirectional"))
    )
    (net (code "95") (name "/PF14") (class "Default")
      (node (ref "J1") (pin "15") (pinfunction "15_15") (pintype "passive"))
      (node (ref "U1") (pin "54") (pinfunction "PF14_54") (pintype "bidirectional"))
    )
    (net (code "96") (name "/PF15") (class "Default")
      (node (ref "J1") (pin "14") (pinfunction "14_14") (pintype "passive"))
      (node (ref "U1") (pin "55") (pinfunction "PF15_55") (pintype "bidirectional"))
    )
    (net (code "97") (name "/PG0") (class "Default")
      (node (ref "J1") (pin "13") (pinfunction "13_13") (pintype "passive"))
      (node (ref "U1") (pin "56") (pinfunction "PG0_56") (pintype "bidirectional"))
    )
    (net (code "98") (name "/PG1") (class "Default")
      (node (ref "J1") (pin "12") (pinfunction "12_12") (pintype "passive"))
      (node (ref "U1") (pin "57") (pinfunction "PG1_57") (pintype "bidirectional"))
    )
    (net (code "99") (name "/PG2") (class "Default")
      (node (ref "J2") (pin "13") (pinfunction "13_13") (pintype "passive"))
      (node (ref "U1") (pin "87") (pinfunction "PG2_87") (pintype "bidirectional"))
    )
    (net (code "100") (name "/PG3") (class "Default")
      (node (ref "J2") (pin "14") (pinfunction "14_14") (pintype "passive"))
      (node (ref "U1") (pin "88") (pinfunction "PG3_88") (pintype "bidirectional"))
    )
    (net (code "101") (name "/PG4") (class "Default")
      (node (ref "J2") (pin "15") (pinfunction "15_15") (pintype "passive"))
      (node (ref "U1") (pin "89") (pinfunction "PG4_89") (pintype "bidirectional"))
    )
    (net (code "102") (name "/PG5") (class "Default")
      (node (ref "J2") (pin "16") (pinfunction "16_16") (pintype "passive"))
      (node (ref "U1") (pin "90") (pinfunction "PG5_90") (pintype "bidirectional"))
    )
    (net (code "103") (name "/PG6") (class "Default")
      (node (ref "J2") (pin "17") (pinfunction "17_17") (pintype "passive"))
      (node (ref "U1") (pin "91") (pinfunction "PG6_91") (pintype "bidirectional"))
    )
    (net (code "104") (name "/PG7") (class "Default")
      (node (ref "J2") (pin "18") (pinfunction "18_18") (pintype "passive"))
      (node (ref "U1") (pin "92") (pinfunction "PG7_92") (pintype "bidirectional"))
    )
    (net (code "105") (name "/PG8") (class "Default")
      (node (ref "J2") (pin "19") (pinfunction "19_19") (pintype "passive"))
      (node (ref "U1") (pin "93") (pinfunction "PG8_93") (pintype "bidirectional"))
    )
    (net (code "106") (name "/PG9") (class "Default")
      (node (ref "J2") (pin "47") (pinfunction "47_47") (pintype "passive"))
      (node (ref "U1") (pin "124") (pinfunction "PG9_124") (pintype "bidirectional"))
    )
    (net (code "107") (name "/PG10") (class "Default")
      (node (ref "J2") (pin "46") (pinfunction "46_46") (pintype "passive"))
      (node (ref "U1") (pin "125") (pinfunction "PG10_125") (pintype "bidirectional"))
    )
    (net (code "108") (name "/PG11") (class "Default")
      (node (ref "J2") (pin "45") (pinfunction "45_45") (pintype "passive"))
      (node (ref "U1") (pin "126") (pinfunction "PG11_126") (pintype "bidirectional"))
    )
    (net (code "109") (name "/PG12") (class "Default")
      (node (ref "J2") (pin "44") (pinfunction "44_44") (pintype "passive"))
      (node (ref "U1") (pin "127") (pinfunction "PG12_127") (pintype "bidirectional"))
    )
    (net (code "110") (name "/PG13") (class "Default")
      (node (ref "J2") (pin "43") (pinfunction "43_43") (pintype "passive"))
      (node (ref "U1") (pin "128") (pinfunction "PG13_128") (pintype "bidirectional"))
    )
    (net (code "111") (name "/PG14") (class "Default")
      (node (ref "J2") (pin "42") (pinfunction "42_42") (pintype "passive"))
      (node (ref "U1") (pin "129") (pinfunction "PG14_129") (pintype "bidirectional"))
    )
    (net (code "112") (name "/PG15") (class "Default")
      (node (ref "J2") (pin "41") (pinfunction "41_41") (pintype "passive"))
      (node (ref "U1") (pin "132") (pinfunction "PG15_132") (pintype "bidirectional"))
    )
    (net (code "113") (name "GND") (class "Default")
      (node (ref "C1") (pin "2") (pinfunction "2_2") (pintype "passive"))
      (node (ref "C10") (pin "1") (pinfunction "1_1") (pintype "passive"))
      (node (ref "C11") (pin "1") (pinfunction "1_1") (pintype "passive"))
      (node (ref "C12") (pin "1") (pinfunction "1_1") (pintype "passive"))
      (node (ref "C13") (pin "1") (pinfunction "1_1") (pintype "passive"))
      (node (ref "C14") (pin "1") (pinfunction "1_1") (pintype "passive"))
      (node (ref "C15") (pin "1") (pinfunction "1_1") (pintype "passive"))
      (node (ref "C16") (pin "1") (pinfunction "1_1") (pintype "passive"))
      (node (ref "C17") (pin "1") (pinfunction "1_1") (pintype "passive"))
      (node (ref "C19") (pin "1") (pinfunction "1_1") (pintype "passive"))
      (node (ref "C2") (pin "1") (pinfunction "1_1") (pintype "passive"))
      (node (ref "C20") (pin "1") (pinfunction "1_1") (pintype "passive"))
      (node (ref "C21") (pin "1") (pinfunction "1_1") (pintype "passive"))
      (node (ref "C22") (pin "1") (pinfunction "1_1") (pintype "passive"))
      (node (ref "C23") (pin "1") (pinfunction "1_1") (pintype "passive"))
      (node (ref "C24") (pin "1") (pinfunction "1_1") (pintype "passive"))
      (node (ref "C25") (pin "1") (pinfunction "1_1") (pintype "passive"))
      (node (ref "C3") (pin "2") (pinfunction "2_2") (pintype "passive"))
      (node (ref "C4") (pin "1") (pinfunction "1_1") (pintype "passive"))
      (node (ref "C5") (pin "1") (pinfunction "1_1") (pintype "passive"))
      (node (ref "C6") (pin "1") (pinfunction "1_1") (pintype "passive"))
      (node (ref "C7") (pin "1") (pinfunction "1_1") (pintype "passive"))
      (node (ref "C8") (pin "1") (pinfunction "1_1") (pintype "passive"))
      (node (ref "C9") (pin "1") (pinfunction "1_1") (pintype "passive"))
      (node (ref "D1") (pin "K") (pinfunction "K_K") (pintype "passive"))
      (node (ref "D2") (pin "1") (pinfunction "1_1") (pintype "passive"))
      (node (ref "D3") (pin "1") (pinfunction "1_1") (pintype "passive"))
      (node (ref "D4") (pin "1") (pinfunction "1_1") (pintype "passive"))
      (node (ref "D5") (pin "K") (pinfunction "K_K") (pintype "passive"))
      (node (ref "IC1") (pin "1") (pinfunction "GND_1") (pintype "passive"))
      (node (ref "J1") (pin "29") (pinfunction "29_29") (pintype "passive"))
      (node (ref "J1") (pin "30") (pinfunction "30_30") (pintype "passive"))
      (node (ref "J2") (pin "30") (pinfunction "30_30") (pintype "passive"))
      (node (ref "J2") (pin "31") (pinfunction "31_31") (pintype "passive"))
      (node (ref "P1") (pin "1") (pinfunction "1_1") (pintype "passive"))
      (node (ref "P2") (pin "5") (pinfunction "GND_5") (pintype "passive"))
      (node (ref "P2") (pin "EH") (pinfunction "EH_EH") (pintype "passive"))
      (node (ref "R1") (pin "1") (pinfunction "1_1") (pintype "passive"))
      (node (ref "SW1") (pin "2") (pinfunction "2_2") (pintype "passive"))
      (node (ref "SW2") (pin "2") (pinfunction "2_2") (pintype "passive"))
      (node (ref "TP3") (pin "1") (pinfunction "1_1") (pintype "passive"))
      (node (ref "U1") (pin "107") (pinfunction "VSS_107") (pintype "power_in"))
      (node (ref "U1") (pin "120") (pinfunction "VSS_120") (pintype "power_in"))
      (node (ref "U1") (pin "130") (pinfunction "VSS_130") (pintype "power_in"))
      (node (ref "U1") (pin "16") (pinfunction "VSS_16") (pintype "power_in"))
      (node (ref "U1") (pin "31") (pinfunction "VSSA_31") (pintype "power_in"))
      (node (ref "U1") (pin "38") (pinfunction "VSS_38") (pintype "power_in"))
      (node (ref "U1") (pin "51") (pinfunction "VSS_51") (pintype "power_in"))
      (node (ref "U1") (pin "61") (pinfunction "VSS_61") (pintype "power_in"))
      (node (ref "U1") (pin "83") (pinfunction "VSS_83") (pintype "power_in"))
      (node (ref "U1") (pin "94") (pinfunction "VSS_94") (pintype "power_in"))
      (node (ref "X1") (pin "2") (pinfunction "GND_2") (pintype "passive"))
    )
    (net (code "114") (name "Net-(D1-PadA)") (class "Default")
      (node (ref "D1") (pin "A") (pinfunction "A_A") (pintype "passive"))
      (node (ref "R3") (pin "1") (pinfunction "1_1") (pintype "passive"))
    )
    (net (code "115") (name "Net-(D5-PadA)") (class "Default")
      (node (ref "D5") (pin "A") (pinfunction "A_A") (pintype "passive"))
      (node (ref "R6") (pin "1") (pinfunction "1_1") (pintype "passive"))
    )
    (net (code "116") (name "Net-(P2-D+)") (class "Default")
      (node (ref "P2") (pin "3") (pinfunction "D+_3") (pintype "passive"))
      (node (ref "R5") (pin "2") (pinfunction "2_2") (pintype "passive"))
    )
    (net (code "117") (name "Net-(P2-D-)") (class "Default")
      (node (ref "P2") (pin "2") (pinfunction "D-_2") (pintype "passive"))
      (node (ref "R4") (pin "2") (pinfunction "2_2") (pintype "passive"))
    )
    (net (code "118") (name "Net-(U1B-BOOT0)") (class "Default")
      (node (ref "R1") (pin "2") (pinfunction "2_2") (pintype "passive"))
      (node (ref "U1") (pin "138") (pinfunction "BOOT0_138") (pintype "input"))
    )
    (net (code "119") (name "Net-(U1B-NRST)") (class "Default")
      (node (ref "C2") (pin "2") (pinfunction "2_2") (pintype "passive"))
      (node (ref "SW1") (pin "1") (pinfunction "1_1") (pintype "passive"))
      (node (ref "U1") (pin "25") (pinfunction "NRST_25") (pintype "bidirectional"))
    )
    (net (code "120") (name "Net-(U1B-PDR_ON)") (class "Default")
      (node (ref "R2") (pin "2") (pinfunction "2_2") (pintype "passive"))
      (node (ref "U1") (pin "143") (pinfunction "PDR_ON_143") (pintype "input"))
    )
    (net (code "121") (name "Net-(U1B-PH0-OSC_IN(PH0))") (class "Default")
      (node (ref "U1") (pin "23") (pinfunction "PH0-OSC_IN(PH0)_23") (pintype "bidirectional"))
      (node (ref "X1") (pin "3") (pinfunction "OSC2_3") (pintype "passive"))
    )
    (net (code "122") (name "Net-(U1B-PH1-OSC_OUT(PH1))") (class "Default")
      (node (ref "U1") (pin "24") (pinfunction "PH1-OSC_OUT(PH1)_24") (pintype "bidirectional"))
      (node (ref "X1") (pin "1") (pinfunction "OSC1_1") (pintype "passive"))
    )
    (net (code "123") (name "Net-(U1B-VCAP_1)") (class "Default")
      (node (ref "C1") (pin "1") (pinfunction "1_1") (pintype "passive"))
      (node (ref "U1") (pin "71") (pinfunction "VCAP_1_71") (pintype "power_in"))
    )
    (net (code "124") (name "Net-(U1B-VCAP_2)") (class "Default")
      (node (ref "C3") (pin "1") (pinfunction "1_1") (pintype "passive"))
      (node (ref "U1") (pin "106") (pinfunction "VCAP_2_106") (pintype "power_in"))
    )
    (net (code "125") (name "VBUS") (class "Default")
      (node (ref "C23") (pin "2") (pinfunction "2_2") (pintype "passive"))
      (node (ref "C24") (pin "2") (pinfunction "2_2") (pintype "passive"))
      (node (ref "C4") (pin "2") (pinfunction "2_2") (pintype "passive"))
      (node (ref "C5") (pin "2") (pinfunction "2_2") (pintype "passive"))
      (node (ref "D4") (pin "2") (pinfunction "2_2") (pintype "passive"))
      (node (ref "IC1") (pin "3") (pinfunction "VIN_3") (pintype "passive"))
      (node (ref "J1") (pin "59") (pinfunction "59_59") (pintype "passive"))
      (node (ref "J1") (pin "60") (pinfunction "60_60") (pintype "passive"))
      (node (ref "P2") (pin "1") (pinfunction "VUSB_1") (pintype "passive"))
      (node (ref "TP1") (pin "1") (pinfunction "1_1") (pintype "passive"))
    )
    (net (code "126") (name "VCC_3V3") (class "Default")
      (node (ref "C10") (pin "2") (pinfunction "2_2") (pintype "passive"))
      (node (ref "C11") (pin "2") (pinfunction "2_2") (pintype "passive"))
      (node (ref "C12") (pin "2") (pinfunction "2_2") (pintype "passive"))
      (node (ref "C13") (pin "2") (pinfunction "2_2") (pintype "passive"))
      (node (ref "C14") (pin "2") (pinfunction "2_2") (pintype "passive"))
      (node (ref "C15") (pin "2") (pinfunction "2_2") (pintype "passive"))
      (node (ref "C16") (pin "2") (pinfunction "2_2") (pintype "passive"))
      (node (ref "C17") (pin "2") (pinfunction "2_2") (pintype "passive"))
      (node (ref "C19") (pin "2") (pinfunction "2_2") (pintype "passive"))
      (node (ref "C20") (pin "2") (pinfunction "2_2") (pintype "passive"))
      (node (ref "C21") (pin "2") (pinfunction "2_2") (pintype "passive"))
      (node (ref "C22") (pin "2") (pinfunction "2_2") (pintype "passive"))
      (node (ref "C6") (pin "2") (pinfunction "2_2") (pintype "passive"))
      (node (ref "C7") (pin "2") (pinfunction "2_2") (pintype "passive"))
      (node (ref "FB1") (pin "1") (pinfunction "1_1") (pintype "passive"))
      (node (ref "IC1") (pin "2") (pinfunction "VOUT_2") (pintype "passive"))
      (node (ref "J1") (pin "57") (pinfunction "57_57") (pintype "passive"))
      (node (ref "J1") (pin "58") (pinfunction "58_58") (pintype "passive"))
      (node (ref "P1") (pin "4") (pinfunction "4_4") (pintype "passive"))
      (node (ref "R2") (pin "1") (pinfunction "1_1") (pintype "passive"))
      (node (ref "R3") (pin "2") (pinfunction "2_2") (pintype "passive"))
      (node (ref "TP2") (pin "1") (pinfunction "1_1") (pintype "passive"))
      (node (ref "U1") (pin "108") (pinfunction "VDD_108") (pintype "power_in"))
      (node (ref "U1") (pin "121") (pinfunction "VDD_121") (pintype "power_in"))
      (node (ref "U1") (pin "131") (pinfunction "VDD_131") (pintype "power_in"))
      (node (ref "U1") (pin "144") (pinfunction "VDD_144") (pintype "power_in"))
      (node (ref "U1") (pin "17") (pinfunction "VDD_17") (pintype "power_in"))
      (node (ref "U1") (pin "30") (pinfunction "VDD_30") (pintype "power_in"))
      (node (ref "U1") (pin "39") (pinfunction "VDD_39") (pintype "power_in"))
      (node (ref "U1") (pin "52") (pinfunction "VDD_52") (pintype "power_in"))
      (node (ref "U1") (pin "6") (pinfunction "VBAT_6") (pintype "power_in"))
      (node (ref "U1") (pin "62") (pinfunction "VDD_62") (pintype "power_in"))
      (node (ref "U1") (pin "72") (pinfunction "VDD_72") (pintype "power_in"))
      (node (ref "U1") (pin "84") (pinfunction "VDD_84") (pintype "power_in"))
      (node (ref "U1") (pin "95") (pinfunction "VDD_95") (pintype "power_in"))
    )
    (net (code "127") (name "VDDA_3V3") (class "Default")
      (node (ref "C8") (pin "2") (pinfunction "2_2") (pintype "passive"))
      (node (ref "C9") (pin "2") (pinfunction "2_2") (pintype "passive"))
      (node (ref "FB1") (pin "2") (pinfunction "2_2") (pintype "passive"))
      (node (ref "U1") (pin "32") (pinfunction "VREF+_32") (pintype "power_in"))
      (node (ref "U1") (pin "33") (pinfunction "VDDA_33") (pintype "power_in"))
    )
    (net (code "128") (name "unconnected-(P2-ID-Pad4)") (class "Default")
      (node (ref "P2") (pin "4") (pinfunction "ID_4") (pintype "passive+no_connect"))
    )
  )
)
